# old_kick_line.net
KiCad netlist of a schematic drawn in EAGLE
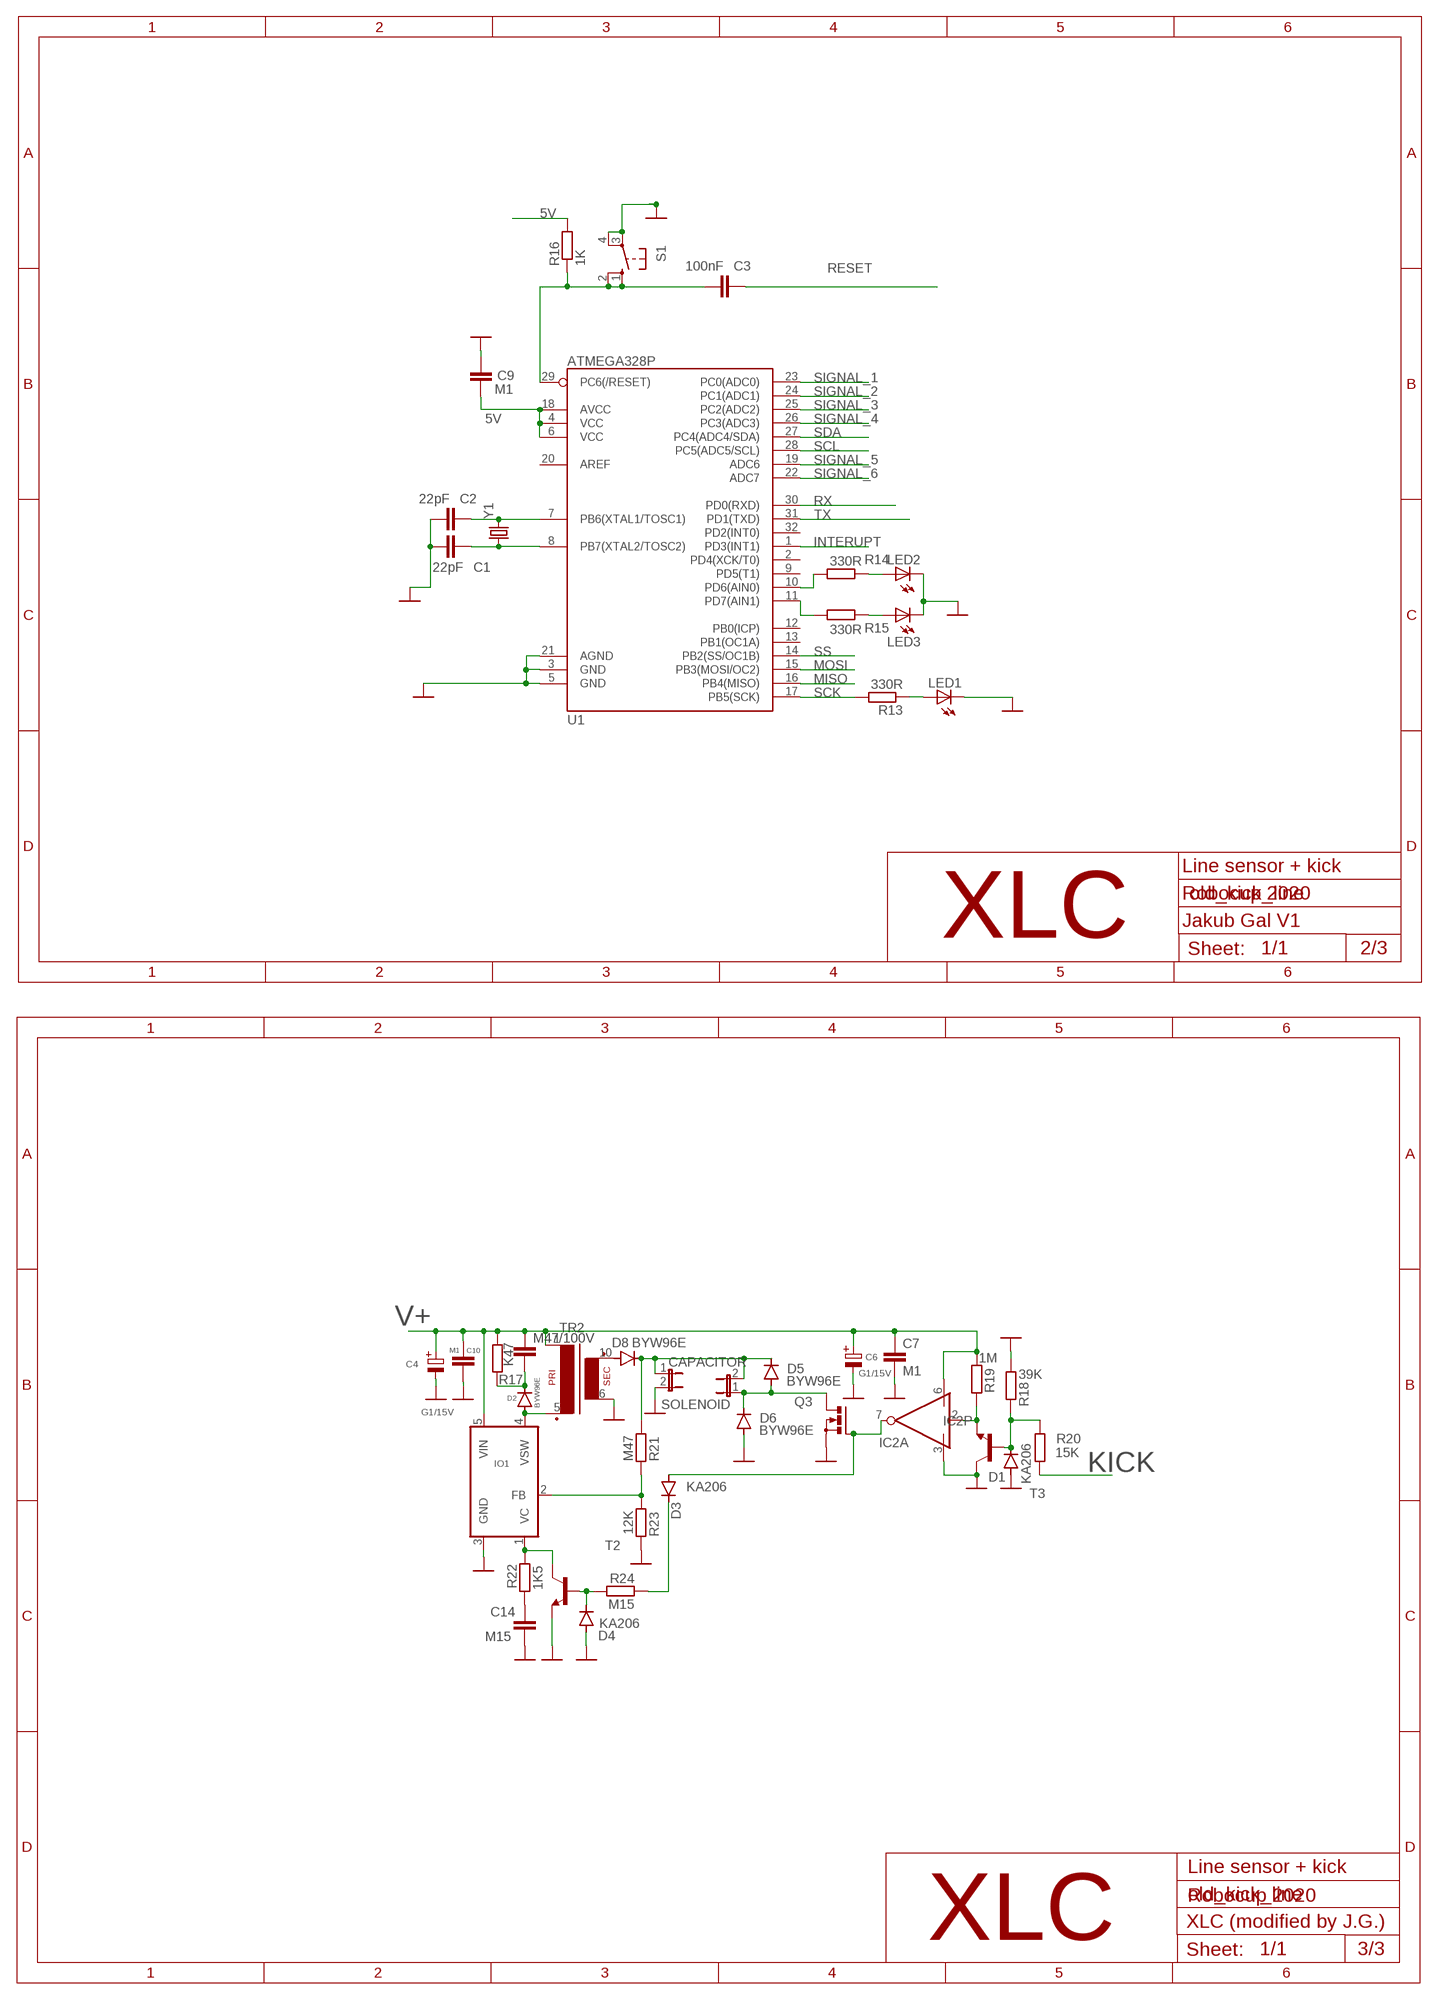
[diagram p0: schematic, sheet 1, part 1 of 2]
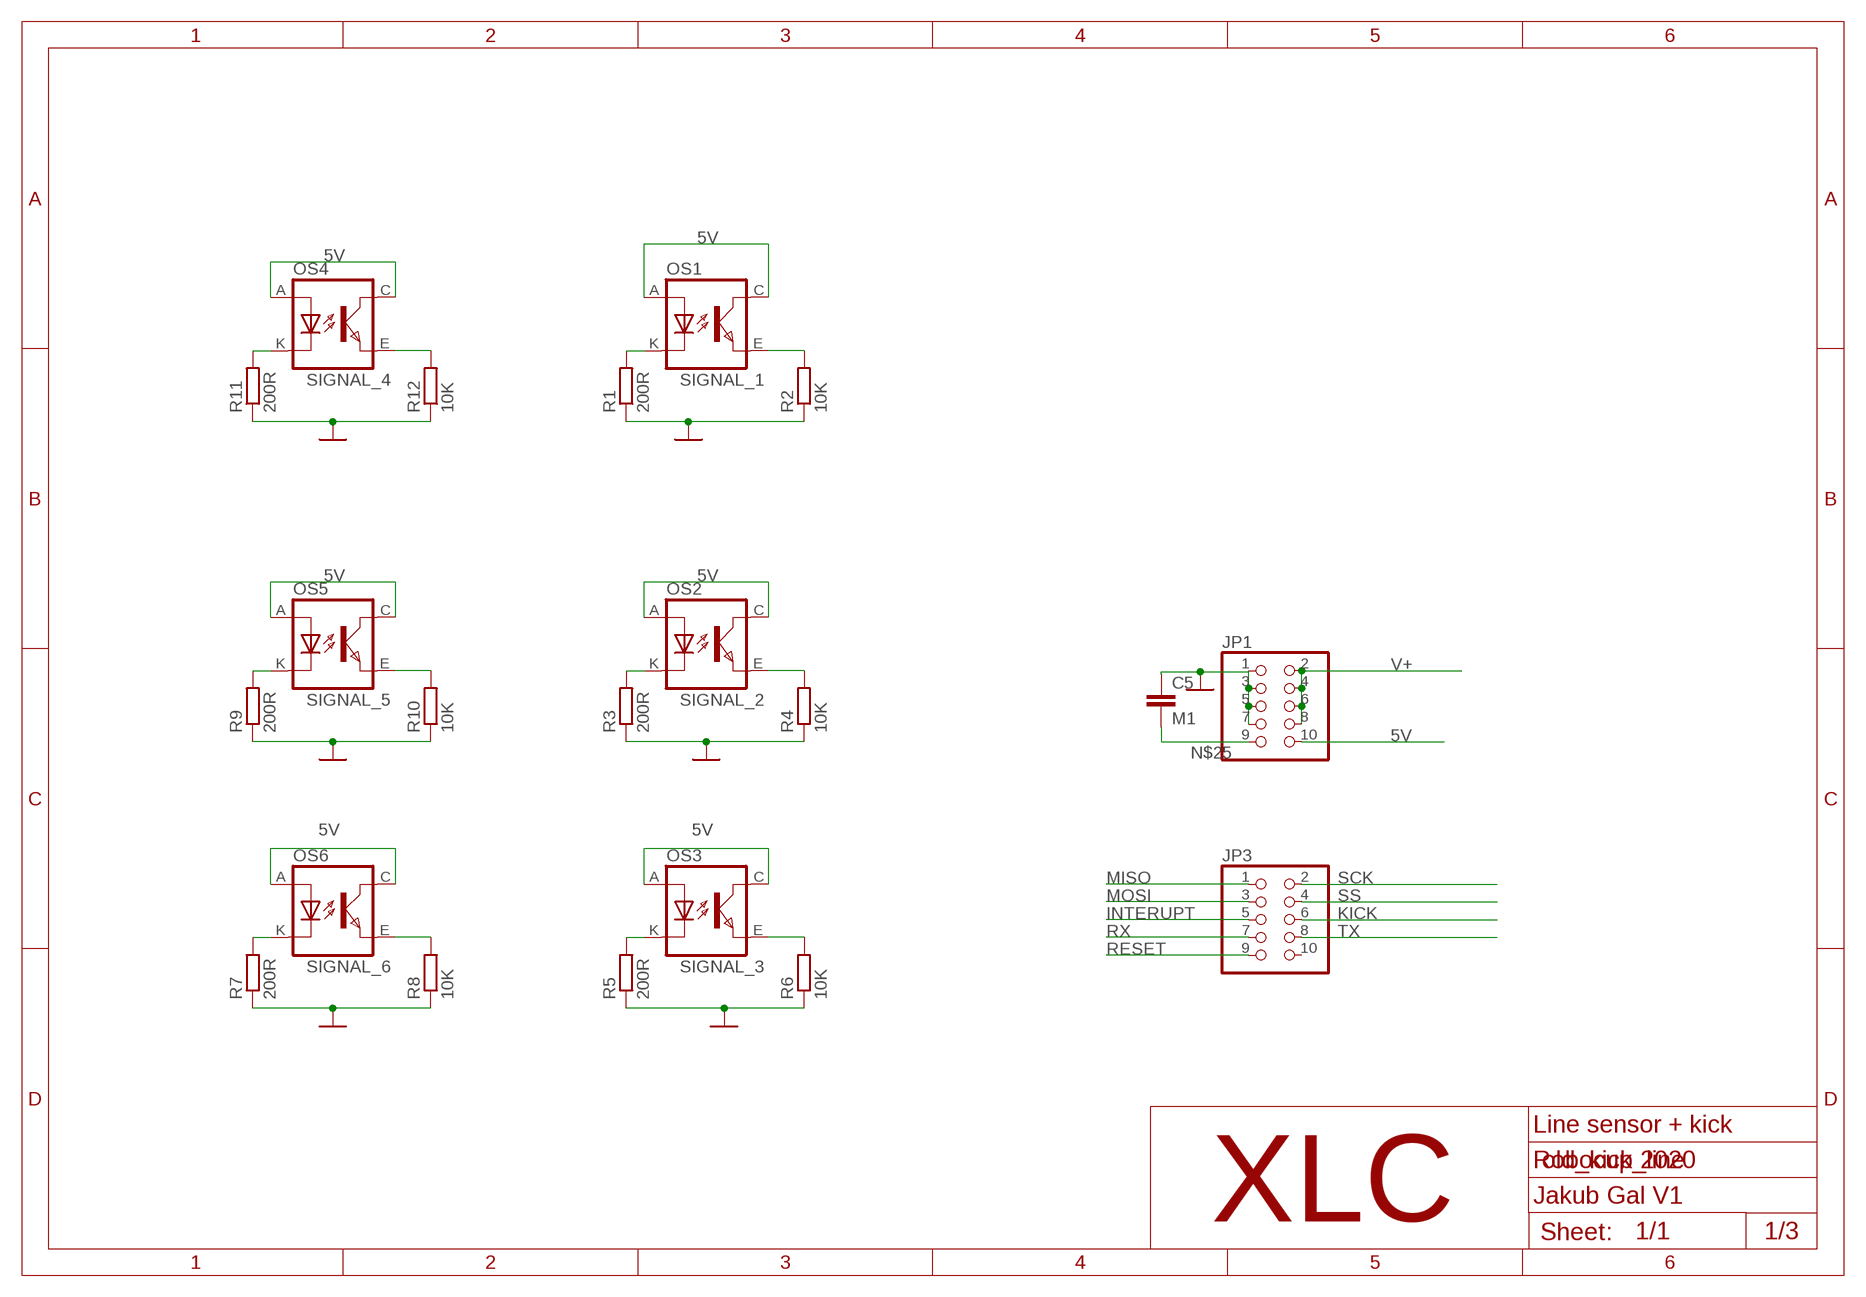
[diagram p1: schematic, sheet 1, part 2 of 2]

(export (version "E")
  (design (tool "Eeschema 10.0.6"))
  (components
    (comp (ref "C1")
      (value "22pF")
      (footprint "eagle-import:C0603")
      (libsource (lib "eagle-import") (part "rcl@1_C-EUC0603"))
    )
    (comp (ref "C2")
      (value "22pF")
      (footprint "eagle-import:C0603")
      (libsource (lib "eagle-import") (part "rcl@1_C-EUC0603"))
    )
    (comp (ref "C3")
      (value "100nF")
      (footprint "eagle-import:C0603")
      (libsource (lib "eagle-import") (part "rcl@1_C-EUC0603"))
    )
    (comp (ref "C4")
      (value "G1/15V")
      (footprint "eagle-import:E-2,5_7-RAD")
      (libsource (lib "eagle-import") (part "KOND-ELEKT-2,5/7"))
    )
    (comp (ref "C5")
      (value "M1")
      (footprint "eagle-import:C0603")
      (libsource (lib "eagle-import") (part "C-EUC0603"))
    )
    (comp (ref "C6")
      (value "G1/15V")
      (footprint "eagle-import:E-2,5_7-RAD")
      (libsource (lib "eagle-import") (part "KOND-ELEKT-2,5/7"))
    )
    (comp (ref "C7")
      (value "M1")
      (footprint "eagle-import:C0805K")
      (libsource (lib "eagle-import") (part "resistor_C-EUC0805K"))
    )
    (comp (ref "C9")
      (value "M1")
      (footprint "eagle-import:C0603")
      (libsource (lib "eagle-import") (part "rcl@1_C-EUC0603"))
    )
    (comp (ref "C10")
      (value "M1")
      (footprint "eagle-import:C0805K")
      (libsource (lib "eagle-import") (part "resistor_C-EUC0805K"))
    )
    (comp (ref "C14")
      (value "M15")
      (footprint "eagle-import:C0805K")
      (libsource (lib "eagle-import") (part "resistor_C-EUC0805K"))
    )
    (comp (ref "CAPACITOR")
      (value "JP1E")
      (footprint "eagle-import:JP1")
      (libsource (lib "eagle-import") (part "JP1E"))
    )
    (comp (ref "D1")
      (value "KA206")
      (footprint "eagle-import:D-7.5")
      (libsource (lib "eagle-import") (part "DIODE-D-7.5"))
    )
    (comp (ref "D2")
      (value "BYW96E")
      (footprint "eagle-import:SOD64-10")
      (libsource (lib "eagle-import") (part "BYW96"))
    )
    (comp (ref "D3")
      (value "KA206")
      (footprint "eagle-import:D-7.5")
      (libsource (lib "eagle-import") (part "DIODE-D-7.5"))
    )
    (comp (ref "D4")
      (value "KA206")
      (footprint "eagle-import:D-7.5")
      (libsource (lib "eagle-import") (part "DIODE-D-7.5"))
    )
    (comp (ref "D5")
      (value "BYW96E")
      (footprint "eagle-import:SOD64-10")
      (libsource (lib "eagle-import") (part "BYW96"))
    )
    (comp (ref "D6")
      (value "BYW96E")
      (footprint "eagle-import:SOD64-10")
      (libsource (lib "eagle-import") (part "BYW96"))
    )
    (comp (ref "D8")
      (value "BYW96E")
      (footprint "eagle-import:SOD64-10")
      (libsource (lib "eagle-import") (part "BYW96"))
    )
    (comp (ref "IC2")
      (value "MIC4423BM")
      (footprint "eagle-import:SO08")
      (libsource (lib "eagle-import") (part "MIC4423BM"))
    )
    (comp (ref "IO1")
      (value "LT1071V")
      (footprint "eagle-import:TO220-5P")
      (libsource (lib "eagle-import") (part "LT1071V"))
    )
    (comp (ref "JP1")
      (value "PINHD-2X5IDC")
      (footprint "eagle-import:2X05_IDC")
      (libsource (lib "eagle-import") (part "PINHD-2X5IDC"))
    )
    (comp (ref "JP3")
      (value "PINHD-2X5IDC")
      (footprint "eagle-import:2X05_IDC")
      (libsource (lib "eagle-import") (part "PINHD-2X5IDC"))
    )
    (comp (ref "LED1")
      (value "LEDCHIPLED_0603")
      (footprint "eagle-import:CHIPLED_0603")
      (libsource (lib "eagle-import") (part "LEDCHIPLED_0603"))
    )
    (comp (ref "LED2")
      (value "LEDCHIPLED_0603")
      (footprint "eagle-import:CHIPLED_0603")
      (libsource (lib "eagle-import") (part "LEDCHIPLED_0603"))
    )
    (comp (ref "LED3")
      (value "LEDCHIPLED_0603")
      (footprint "eagle-import:CHIPLED_0603")
      (libsource (lib "eagle-import") (part "LEDCHIPLED_0603"))
    )
    (comp (ref "M47/100V")
      (value "C-EUC0805K")
      (footprint "eagle-import:C0805K")
      (libsource (lib "eagle-import") (part "resistor_C-EUC0805K"))
    )
    (comp (ref "OS1")
      (value "TCRT5000")
      (footprint "eagle-import:TCRT5000")
      (libsource (lib "eagle-import") (part "TCRT5000"))
    )
    (comp (ref "OS2")
      (value "TCRT5000")
      (footprint "eagle-import:TCRT5000")
      (libsource (lib "eagle-import") (part "TCRT5000"))
    )
    (comp (ref "OS3")
      (value "TCRT5000")
      (footprint "eagle-import:TCRT5000")
      (libsource (lib "eagle-import") (part "TCRT5000"))
    )
    (comp (ref "OS4")
      (value "TCRT5000")
      (footprint "eagle-import:TCRT5000")
      (fields (field (name "SPICEPREFIX") "O"))
      (libsource (lib "eagle-import") (part "TCRT5000"))
    )
    (comp (ref "OS5")
      (value "TCRT5000")
      (footprint "eagle-import:TCRT5000")
      (libsource (lib "eagle-import") (part "TCRT5000"))
    )
    (comp (ref "OS6")
      (value "TCRT5000")
      (footprint "eagle-import:TCRT5000")
      (fields (field (name "SPICEPREFIX") "O"))
      (libsource (lib "eagle-import") (part "TCRT5000"))
    )
    (comp (ref "Q3")
      (value "PMOSFET_NTO220BV")
      (footprint "eagle-import:TO220BV")
      (libsource (lib "eagle-import") (part "PMOSFET_NTO220BV"))
    )
    (comp (ref "R1")
      (value "200R")
      (footprint "eagle-import:R0603")
      (libsource (lib "eagle-import") (part "R-EU_R0603"))
    )
    (comp (ref "R2")
      (value "10K")
      (footprint "eagle-import:R0603")
      (libsource (lib "eagle-import") (part "R-EU_R0603"))
    )
    (comp (ref "R3")
      (value "200R")
      (footprint "eagle-import:R0603")
      (libsource (lib "eagle-import") (part "R-EU_R0603"))
    )
    (comp (ref "R4")
      (value "10K")
      (footprint "eagle-import:R0603")
      (libsource (lib "eagle-import") (part "R-EU_R0603"))
    )
    (comp (ref "R5")
      (value "200R")
      (footprint "eagle-import:R0603")
      (libsource (lib "eagle-import") (part "R-EU_R0603"))
    )
    (comp (ref "R6")
      (value "10K")
      (footprint "eagle-import:R0603")
      (libsource (lib "eagle-import") (part "R-EU_R0603"))
    )
    (comp (ref "R7")
      (value "200R")
      (footprint "eagle-import:R0603")
      (libsource (lib "eagle-import") (part "R-EU_R0603"))
    )
    (comp (ref "R8")
      (value "10K")
      (footprint "eagle-import:R0603")
      (libsource (lib "eagle-import") (part "R-EU_R0603"))
    )
    (comp (ref "R9")
      (value "200R")
      (footprint "eagle-import:R0603")
      (libsource (lib "eagle-import") (part "R-EU_R0603"))
    )
    (comp (ref "R10")
      (value "10K")
      (footprint "eagle-import:R0603")
      (libsource (lib "eagle-import") (part "R-EU_R0603"))
    )
    (comp (ref "R11")
      (value "200R")
      (footprint "eagle-import:R0603")
      (libsource (lib "eagle-import") (part "R-EU_R0603"))
    )
    (comp (ref "R12")
      (value "10K")
      (footprint "eagle-import:R0603")
      (libsource (lib "eagle-import") (part "R-EU_R0603"))
    )
    (comp (ref "R13")
      (value "330R")
      (footprint "eagle-import:R0603")
      (libsource (lib "eagle-import") (part "R-EU_R0603"))
    )
    (comp (ref "R14")
      (value "330R")
      (footprint "eagle-import:R0603")
      (libsource (lib "eagle-import") (part "R-EU_R0603"))
    )
    (comp (ref "R15")
      (value "330R")
      (footprint "eagle-import:R0603")
      (libsource (lib "eagle-import") (part "R-EU_R0603"))
    )
    (comp (ref "R16")
      (value "1K")
      (footprint "eagle-import:R0603")
      (libsource (lib "eagle-import") (part "R-EU_R0603"))
    )
    (comp (ref "R17")
      (value "K47")
      (footprint "eagle-import:R0603")
      (libsource (lib "eagle-import") (part "resistor_R-EU_R0603"))
    )
    (comp (ref "R18")
      (value "39K")
      (footprint "eagle-import:R0603")
      (libsource (lib "eagle-import") (part "resistor_R-EU_R0603"))
    )
    (comp (ref "R19")
      (value "1M")
      (footprint "eagle-import:R0603")
      (libsource (lib "eagle-import") (part "resistor_R-EU_R0603"))
    )
    (comp (ref "R20")
      (value "15K")
      (footprint "eagle-import:R0603")
      (libsource (lib "eagle-import") (part "resistor_R-EU_R0603"))
    )
    (comp (ref "R21")
      (value "M47")
      (footprint "eagle-import:R0603")
      (libsource (lib "eagle-import") (part "resistor_R-EU_R0603"))
    )
    (comp (ref "R22")
      (value "1K5")
      (footprint "eagle-import:R0603")
      (libsource (lib "eagle-import") (part "resistor_R-EU_R0603"))
    )
    (comp (ref "R23")
      (value "12K")
      (footprint "eagle-import:R0603")
      (libsource (lib "eagle-import") (part "resistor_R-EU_R0603"))
    )
    (comp (ref "R24")
      (value "M15")
      (footprint "eagle-import:R0603")
      (libsource (lib "eagle-import") (part "resistor_R-EU_R0603"))
    )
    (comp (ref "S1")
      (value "10-XX")
      (footprint "eagle-import:B3F-10XX")
      (fields (field (name "MPN") "B3F-1000"))
      (libsource (lib "eagle-import") (part "10-XX"))
    )
    (comp (ref "SOLENOID")
      (value "JP1E")
      (footprint "eagle-import:JP1")
      (libsource (lib "eagle-import") (part "JP1E"))
    )
    (comp (ref "T2")
      (value "-NPN-SC59-BEC")
      (footprint "eagle-import:SC59-BEC")
      (libsource (lib "eagle-import") (part "-NPN-SC59-BEC"))
    )
    (comp (ref "T3")
      (value "-NPN-SC59-BEC")
      (footprint "eagle-import:SC59-BEC")
      (libsource (lib "eagle-import") (part "-NPN-SC59-BEC"))
    )
    (comp (ref "TR2")
      (value "TRAFO-E10-R\"\"")
      (footprint "eagle-import:TRAFO-EE17X20")
      (libsource (lib "eagle-import") (part "TRAFO-E10-R{dblquote}{dblquote}"))
    )
    (comp (ref "U1")
      (value "ATMEGA328P")
      (footprint "eagle-import:TQFP32-08")
      (libsource (lib "eagle-import") (part "ATMEGA328_SMT"))
    )
    (comp (ref "Y1")
      (value "CRYSTALHC49US")
      (footprint "eagle-import:HC49US")
      (libsource (lib "eagle-import") (part "CRYSTALHC49US"))
    )
  )
  (nets
    (net (code "1") (name "/5V") (class "Default")
      (node (ref "C9") (pin "1") (pinfunction "1_1") (pintype "passive"))
      (node (ref "JP1") (pin "10") (pinfunction "10_10") (pintype "passive"))
      (node (ref "OS1") (pin "A") (pinfunction "ANODE_A") (pintype "passive"))
      (node (ref "OS1") (pin "C") (pinfunction "COLLECTOR_C") (pintype "passive"))
      (node (ref "OS2") (pin "A") (pinfunction "ANODE_A") (pintype "passive"))
      (node (ref "OS2") (pin "C") (pinfunction "COLLECTOR_C") (pintype "passive"))
      (node (ref "OS3") (pin "A") (pinfunction "ANODE_A") (pintype "passive"))
      (node (ref "OS3") (pin "C") (pinfunction "COLLECTOR_C") (pintype "passive"))
      (node (ref "OS4") (pin "A") (pinfunction "ANODE_A") (pintype "passive"))
      (node (ref "OS4") (pin "C") (pinfunction "COLLECTOR_C") (pintype "passive"))
      (node (ref "OS5") (pin "A") (pinfunction "ANODE_A") (pintype "passive"))
      (node (ref "OS5") (pin "C") (pinfunction "COLLECTOR_C") (pintype "passive"))
      (node (ref "OS6") (pin "A") (pinfunction "ANODE_A") (pintype "passive"))
      (node (ref "OS6") (pin "C") (pinfunction "COLLECTOR_C") (pintype "passive"))
      (node (ref "R16") (pin "2") (pinfunction "2_2") (pintype "passive"))
      (node (ref "U1") (pin "18") (pinfunction "AVCC_18") (pintype "bidirectional"))
      (node (ref "U1") (pin "4") (pinfunction "VCC_4") (pintype "bidirectional"))
      (node (ref "U1") (pin "6") (pinfunction "VCC_6") (pintype "bidirectional"))
    )
    (net (code "2") (name "/INTERUPT") (class "Default")
      (node (ref "JP3") (pin "5") (pinfunction "5_5") (pintype "passive"))
      (node (ref "U1") (pin "1") (pinfunction "PD3(INT1)_1") (pintype "bidirectional"))
    )
    (net (code "3") (name "/KICK") (class "Default")
      (node (ref "JP3") (pin "6") (pinfunction "6_6") (pintype "passive"))
      (node (ref "R20") (pin "1") (pinfunction "1_1") (pintype "passive"))
    )
    (net (code "4") (name "/MISO") (class "Default")
      (node (ref "JP3") (pin "1") (pinfunction "1_1") (pintype "passive"))
      (node (ref "U1") (pin "16") (pinfunction "PB4(MISO)_16") (pintype "bidirectional"))
    )
    (net (code "5") (name "/MOSI") (class "Default")
      (node (ref "JP3") (pin "3") (pinfunction "3_3") (pintype "passive"))
      (node (ref "U1") (pin "15") (pinfunction "PB3(MOSI/OC2)_15") (pintype "bidirectional"))
    )
    (net (code "6") (name "/N$25") (class "Default")
      (node (ref "C5") (pin "2") (pinfunction "2_2") (pintype "passive"))
      (node (ref "JP1") (pin "9") (pinfunction "9_9") (pintype "passive"))
    )
    (net (code "7") (name "/RESET") (class "Default")
      (node (ref "C3") (pin "2") (pinfunction "2_2") (pintype "passive"))
      (node (ref "JP3") (pin "9") (pinfunction "9_9") (pintype "passive"))
    )
    (net (code "8") (name "/RX") (class "Default")
      (node (ref "JP3") (pin "7") (pinfunction "7_7") (pintype "passive"))
      (node (ref "U1") (pin "30") (pinfunction "PD0(RXD)_30") (pintype "bidirectional"))
    )
    (net (code "9") (name "/SCK") (class "Default")
      (node (ref "JP3") (pin "2") (pinfunction "2_2") (pintype "passive"))
      (node (ref "R13") (pin "2") (pinfunction "2_2") (pintype "passive"))
      (node (ref "U1") (pin "17") (pinfunction "PB5(SCK)_17") (pintype "bidirectional"))
    )
    (net (code "10") (name "/SCL") (class "Default")
      (node (ref "U1") (pin "28") (pinfunction "PC5(ADC5/SCL)_28") (pintype "bidirectional"))
    )
    (net (code "11") (name "/SDA") (class "Default")
      (node (ref "U1") (pin "27") (pinfunction "PC4(ADC4/SDA)_27") (pintype "bidirectional"))
    )
    (net (code "12") (name "/SIGNAL_1") (class "Default")
      (node (ref "OS1") (pin "E") (pinfunction "EMITTER_E") (pintype "passive"))
      (node (ref "R2") (pin "2") (pinfunction "2_2") (pintype "passive"))
      (node (ref "U1") (pin "23") (pinfunction "PC0(ADC0)_23") (pintype "bidirectional"))
    )
    (net (code "13") (name "/SIGNAL_2") (class "Default")
      (node (ref "OS2") (pin "E") (pinfunction "EMITTER_E") (pintype "passive"))
      (node (ref "R4") (pin "2") (pinfunction "2_2") (pintype "passive"))
      (node (ref "U1") (pin "24") (pinfunction "PC1(ADC1)_24") (pintype "bidirectional"))
    )
    (net (code "14") (name "/SIGNAL_3") (class "Default")
      (node (ref "OS3") (pin "E") (pinfunction "EMITTER_E") (pintype "passive"))
      (node (ref "R6") (pin "2") (pinfunction "2_2") (pintype "passive"))
      (node (ref "U1") (pin "25") (pinfunction "PC2(ADC2)_25") (pintype "bidirectional"))
    )
    (net (code "15") (name "/SIGNAL_4") (class "Default")
      (node (ref "OS4") (pin "E") (pinfunction "EMITTER_E") (pintype "passive"))
      (node (ref "R12") (pin "2") (pinfunction "2_2") (pintype "passive"))
      (node (ref "U1") (pin "26") (pinfunction "PC3(ADC3)_26") (pintype "bidirectional"))
    )
    (net (code "16") (name "/SIGNAL_5") (class "Default")
      (node (ref "OS5") (pin "E") (pinfunction "EMITTER_E") (pintype "passive"))
      (node (ref "R10") (pin "2") (pinfunction "2_2") (pintype "passive"))
      (node (ref "U1") (pin "19") (pinfunction "ADC6_19") (pintype "bidirectional"))
    )
    (net (code "17") (name "/SIGNAL_6") (class "Default")
      (node (ref "OS6") (pin "E") (pinfunction "EMITTER_E") (pintype "passive"))
      (node (ref "R8") (pin "2") (pinfunction "2_2") (pintype "passive"))
      (node (ref "U1") (pin "22") (pinfunction "ADC7_22") (pintype "bidirectional"))
    )
    (net (code "18") (name "/SS") (class "Default")
      (node (ref "JP3") (pin "4") (pinfunction "4_4") (pintype "passive"))
      (node (ref "U1") (pin "14") (pinfunction "PB2(SS/OC1B)_14") (pintype "bidirectional"))
    )
    (net (code "19") (name "/TX") (class "Default")
      (node (ref "JP3") (pin "8") (pinfunction "8_8") (pintype "passive"))
      (node (ref "U1") (pin "31") (pinfunction "PD1(TXD)_31") (pintype "bidirectional"))
    )
    (net (code "20") (name "/V+") (class "Default")
      (node (ref "C10") (pin "1") (pinfunction "1_1") (pintype "passive"))
      (node (ref "C4") (pin "+") (pinfunction "+_+") (pintype "passive"))
      (node (ref "C6") (pin "+") (pinfunction "+_+") (pintype "passive"))
      (node (ref "C7") (pin "1") (pinfunction "1_1") (pintype "passive"))
      (node (ref "IC2") (pin "6") (pinfunction "V+_6") (pintype "power_in"))
      (node (ref "IO1") (pin "5") (pinfunction "VIN_5") (pintype "power_in"))
      (node (ref "JP1") (pin "2") (pinfunction "2_2") (pintype "passive"))
      (node (ref "JP1") (pin "4") (pinfunction "4_4") (pintype "passive"))
      (node (ref "JP1") (pin "6") (pinfunction "6_6") (pintype "passive"))
      (node (ref "JP1") (pin "8") (pinfunction "8_8") (pintype "passive"))
      (node (ref "M47/100V") (pin "1") (pinfunction "1_1") (pintype "passive"))
      (node (ref "R17") (pin "1") (pinfunction "1_1") (pintype "passive"))
      (node (ref "R19") (pin "2") (pinfunction "2_2") (pintype "passive"))
      (node (ref "TR2") (pin "1") (pinfunction "1_1") (pintype "passive"))
    )
    (net (code "21") (name "GND") (class "Default")
      (node (ref "C1") (pin "1") (pinfunction "1_1") (pintype "passive"))
      (node (ref "C10") (pin "2") (pinfunction "2_2") (pintype "passive"))
      (node (ref "C14") (pin "2") (pinfunction "2_2") (pintype "passive"))
      (node (ref "C2") (pin "1") (pinfunction "1_1") (pintype "passive"))
      (node (ref "C4") (pin "-") (pinfunction "-_-") (pintype "passive"))
      (node (ref "C5") (pin "1") (pinfunction "1_1") (pintype "passive"))
      (node (ref "C6") (pin "-") (pinfunction "-_-") (pintype "passive"))
      (node (ref "C7") (pin "2") (pinfunction "2_2") (pintype "passive"))
      (node (ref "C9") (pin "2") (pinfunction "2_2") (pintype "passive"))
      (node (ref "CAPACITOR") (pin "2") (pinfunction "2_2") (pintype "passive"))
      (node (ref "D1") (pin "A") (pinfunction "A_A") (pintype "passive"))
      (node (ref "D4") (pin "A") (pinfunction "A_A") (pintype "passive"))
      (node (ref "D6") (pin "A") (pinfunction "A_A") (pintype "passive"))
      (node (ref "IC2") (pin "3") (pinfunction "GND_3") (pintype "power_in"))
      (node (ref "IO1") (pin "3") (pinfunction "GND_3") (pintype "power_in"))
      (node (ref "JP1") (pin "1") (pinfunction "1_1") (pintype "passive"))
      (node (ref "JP1") (pin "3") (pinfunction "3_3") (pintype "passive"))
      (node (ref "JP1") (pin "5") (pinfunction "5_5") (pintype "passive"))
      (node (ref "JP1") (pin "7") (pinfunction "7_7") (pintype "passive"))
      (node (ref "LED1") (pin "C") (pinfunction "C_C") (pintype "passive"))
      (node (ref "LED2") (pin "C") (pinfunction "C_C") (pintype "passive"))
      (node (ref "LED3") (pin "C") (pinfunction "C_C") (pintype "passive"))
      (node (ref "Q3") (pin "S") (pinfunction "S_S") (pintype "passive"))
      (node (ref "R1") (pin "1") (pinfunction "1_1") (pintype "passive"))
      (node (ref "R10") (pin "1") (pinfunction "1_1") (pintype "passive"))
      (node (ref "R11") (pin "1") (pinfunction "1_1") (pintype "passive"))
      (node (ref "R12") (pin "1") (pinfunction "1_1") (pintype "passive"))
      (node (ref "R18") (pin "2") (pinfunction "2_2") (pintype "passive"))
      (node (ref "R2") (pin "1") (pinfunction "1_1") (pintype "passive"))
      (node (ref "R23") (pin "1") (pinfunction "1_1") (pintype "passive"))
      (node (ref "R3") (pin "1") (pinfunction "1_1") (pintype "passive"))
      (node (ref "R4") (pin "1") (pinfunction "1_1") (pintype "passive"))
      (node (ref "R5") (pin "1") (pinfunction "1_1") (pintype "passive"))
      (node (ref "R6") (pin "1") (pinfunction "1_1") (pintype "passive"))
      (node (ref "R7") (pin "1") (pinfunction "1_1") (pintype "passive"))
      (node (ref "R8") (pin "1") (pinfunction "1_1") (pintype "passive"))
      (node (ref "R9") (pin "1") (pinfunction "1_1") (pintype "passive"))
      (node (ref "S1") (pin "3") (pinfunction "P_3") (pintype "passive"))
      (node (ref "S1") (pin "4") (pinfunction "P1_4") (pintype "passive"))
      (node (ref "T2") (pin "E") (pinfunction "E_E") (pintype "passive"))
      (node (ref "T3") (pin "C") (pinfunction "C_C") (pintype "passive"))
      (node (ref "TR2") (pin "6") (pinfunction "3_6") (pintype "passive"))
      (node (ref "U1") (pin "21") (pinfunction "AGND_21") (pintype "bidirectional"))
      (node (ref "U1") (pin "3") (pinfunction "GND_3") (pintype "bidirectional"))
      (node (ref "U1") (pin "5") (pinfunction "GND_5") (pintype "bidirectional"))
    )
    (net (code "22") (name "Net-(C14-Pad1)") (class "Default")
      (node (ref "C14") (pin "1") (pinfunction "1_1") (pintype "passive"))
      (node (ref "R22") (pin "2") (pinfunction "2_2") (pintype "passive"))
    )
    (net (code "23") (name "Net-(CAPACITOR-Pad1)") (class "Default")
      (node (ref "CAPACITOR") (pin "1") (pinfunction "1_1") (pintype "passive"))
      (node (ref "D5") (pin "C") (pinfunction "C_C") (pintype "passive"))
      (node (ref "D8") (pin "C") (pinfunction "C_C") (pintype "passive"))
      (node (ref "R21") (pin "2") (pinfunction "2_2") (pintype "passive"))
      (node (ref "SOLENOID") (pin "2") (pinfunction "2_2") (pintype "passive"))
    )
    (net (code "24") (name "Net-(D1-PadC)") (class "Default")
      (node (ref "D1") (pin "C") (pinfunction "C_C") (pintype "passive"))
      (node (ref "R18") (pin "1") (pinfunction "1_1") (pintype "passive"))
      (node (ref "R20") (pin "2") (pinfunction "2_2") (pintype "passive"))
      (node (ref "T3") (pin "B") (pinfunction "B_B") (pintype "passive"))
    )
    (net (code "25") (name "Net-(D2-PadC)") (class "Default")
      (node (ref "D2") (pin "C") (pinfunction "C_C") (pintype "passive"))
      (node (ref "M47/100V") (pin "2") (pinfunction "2_2") (pintype "passive"))
      (node (ref "R17") (pin "2") (pinfunction "2_2") (pintype "passive"))
    )
    (net (code "26") (name "Net-(D3-PadC)") (class "Default")
      (node (ref "D3") (pin "C") (pinfunction "C_C") (pintype "passive"))
      (node (ref "R24") (pin "1") (pinfunction "1_1") (pintype "passive"))
    )
    (net (code "27") (name "Net-(D4-PadC)") (class "Default")
      (node (ref "D4") (pin "C") (pinfunction "C_C") (pintype "passive"))
      (node (ref "R24") (pin "2") (pinfunction "2_2") (pintype "passive"))
      (node (ref "T2") (pin "B") (pinfunction "B_B") (pintype "passive"))
    )
    (net (code "28") (name "Net-(D5-PadA)") (class "Default")
      (node (ref "D5") (pin "A") (pinfunction "A_A") (pintype "passive"))
      (node (ref "D6") (pin "C") (pinfunction "C_C") (pintype "passive"))
      (node (ref "Q3") (pin "D") (pinfunction "D_D") (pintype "passive"))
      (node (ref "SOLENOID") (pin "1") (pinfunction "1_1") (pintype "passive"))
    )
    (net (code "29") (name "Net-(IC2A-IN)") (class "Default")
      (node (ref "IC2") (pin "2") (pinfunction "IN_2") (pintype "input"))
      (node (ref "R19") (pin "1") (pinfunction "1_1") (pintype "passive"))
      (node (ref "T3") (pin "E") (pinfunction "E_E") (pintype "passive"))
    )
    (net (code "30") (name "Net-(IC2A-OUT)") (class "Default")
      (node (ref "D3") (pin "A") (pinfunction "A_A") (pintype "passive"))
      (node (ref "IC2") (pin "7") (pinfunction "OUT_7") (pintype "output"))
      (node (ref "Q3") (pin "G") (pinfunction "G_G") (pintype "passive"))
    )
    (net (code "31") (name "Net-(IO1-FB)") (class "Default")
      (node (ref "IO1") (pin "2") (pinfunction "FB_2") (pintype "input"))
      (node (ref "R21") (pin "1") (pinfunction "1_1") (pintype "passive"))
      (node (ref "R23") (pin "2") (pinfunction "2_2") (pintype "passive"))
    )
    (net (code "32") (name "Net-(IO1-VC)") (class "Default")
      (node (ref "IO1") (pin "1") (pinfunction "VC_1") (pintype "input"))
      (node (ref "R22") (pin "1") (pinfunction "1_1") (pintype "passive"))
      (node (ref "T2") (pin "C") (pinfunction "C_C") (pintype "passive"))
    )
    (net (code "33") (name "Net-(IO1-VSW)") (class "Default")
      (node (ref "D2") (pin "A") (pinfunction "A_A") (pintype "passive"))
      (node (ref "IO1") (pin "4") (pinfunction "VSW_4") (pintype "output"))
      (node (ref "TR2") (pin "5") (pinfunction "2_5") (pintype "passive"))
    )
    (net (code "34") (name "Net-(LED1-PadA)") (class "Default")
      (node (ref "LED1") (pin "A") (pinfunction "A_A") (pintype "passive"))
      (node (ref "R13") (pin "1") (pinfunction "1_1") (pintype "passive"))
    )
    (net (code "35") (name "Net-(LED2-PadA)") (class "Default")
      (node (ref "LED2") (pin "A") (pinfunction "A_A") (pintype "passive"))
      (node (ref "R14") (pin "1") (pinfunction "1_1") (pintype "passive"))
    )
    (net (code "36") (name "Net-(LED3-PadA)") (class "Default")
      (node (ref "LED3") (pin "A") (pinfunction "A_A") (pintype "passive"))
      (node (ref "R15") (pin "1") (pinfunction "1_1") (pintype "passive"))
    )
    (net (code "37") (name "Net-(OS1-CATHODE)") (class "Default")
      (node (ref "OS1") (pin "K") (pinfunction "CATHODE_K") (pintype "passive"))
      (node (ref "R1") (pin "2") (pinfunction "2_2") (pintype "passive"))
    )
    (net (code "38") (name "Net-(OS2-CATHODE)") (class "Default")
      (node (ref "OS2") (pin "K") (pinfunction "CATHODE_K") (pintype "passive"))
      (node (ref "R3") (pin "2") (pinfunction "2_2") (pintype "passive"))
    )
    (net (code "39") (name "Net-(OS3-CATHODE)") (class "Default")
      (node (ref "OS3") (pin "K") (pinfunction "CATHODE_K") (pintype "passive"))
      (node (ref "R5") (pin "2") (pinfunction "2_2") (pintype "passive"))
    )
    (net (code "40") (name "Net-(OS4-CATHODE)") (class "Default")
      (node (ref "OS4") (pin "K") (pinfunction "CATHODE_K") (pintype "passive"))
      (node (ref "R11") (pin "2") (pinfunction "2_2") (pintype "passive"))
    )
    (net (code "41") (name "Net-(OS5-CATHODE)") (class "Default")
      (node (ref "OS5") (pin "K") (pinfunction "CATHODE_K") (pintype "passive"))
      (node (ref "R9") (pin "2") (pinfunction "2_2") (pintype "passive"))
    )
    (net (code "42") (name "Net-(OS6-CATHODE)") (class "Default")
      (node (ref "OS6") (pin "K") (pinfunction "CATHODE_K") (pintype "passive"))
      (node (ref "R7") (pin "2") (pinfunction "2_2") (pintype "passive"))
    )
    (net (code "43") (name "Net-(S1-S)") (class "Default")
      (node (ref "C3") (pin "1") (pinfunction "1_1") (pintype "passive"))
      (node (ref "R16") (pin "1") (pinfunction "1_1") (pintype "passive"))
      (node (ref "S1") (pin "1") (pinfunction "S_1") (pintype "passive"))
      (node (ref "S1") (pin "2") (pinfunction "S1_2") (pintype "passive"))
      (node (ref "U1") (pin "29") (pinfunction "PC6(/RESET)_29") (pintype "bidirectional"))
    )
    (net (code "44") (name "Net-(TR2-4)") (class "Default")
      (node (ref "D8") (pin "A") (pinfunction "A_A") (pintype "passive"))
      (node (ref "TR2") (pin "10") (pinfunction "4_10") (pintype "passive"))
    )
    (net (code "45") (name "Net-(U1-PB6(XTAL1{slash}TOSC1))") (class "Default")
      (node (ref "C2") (pin "2") (pinfunction "2_2") (pintype "passive"))
      (node (ref "U1") (pin "7") (pinfunction "PB6(XTAL1/TOSC1)_7") (pintype "bidirectional"))
      (node (ref "Y1") (pin "2") (pinfunction "2_2") (pintype "passive"))
    )
    (net (code "46") (name "Net-(U1-PB7(XTAL2{slash}TOSC2))") (class "Default")
      (node (ref "C1") (pin "2") (pinfunction "2_2") (pintype "passive"))
      (node (ref "U1") (pin "8") (pinfunction "PB7(XTAL2/TOSC2)_8") (pintype "bidirectional"))
      (node (ref "Y1") (pin "1") (pinfunction "1_1") (pintype "passive"))
    )
    (net (code "47") (name "Net-(U1-PD6(AIN0))") (class "Default")
      (node (ref "R14") (pin "2") (pinfunction "2_2") (pintype "passive"))
      (node (ref "U1") (pin "10") (pinfunction "PD6(AIN0)_10") (pintype "bidirectional"))
    )
    (net (code "48") (name "Net-(U1-PD7(AIN1))") (class "Default")
      (node (ref "R15") (pin "2") (pinfunction "2_2") (pintype "passive"))
      (node (ref "U1") (pin "11") (pinfunction "PD7(AIN1)_11") (pintype "bidirectional"))
    )
    (net (code "49") (name "unconnected-(JP3-Pad10)") (class "Default")
      (node (ref "JP3") (pin "10") (pinfunction "10_10") (pintype "passive"))
    )
    (net (code "50") (name "unconnected-(U1-AREF-Pad20)") (class "Default")
      (node (ref "U1") (pin "20") (pinfunction "AREF_20") (pintype "bidirectional"))
    )
    (net (code "51") (name "unconnected-(U1-PB0(ICP)-Pad12)") (class "Default")
      (node (ref "U1") (pin "12") (pinfunction "PB0(ICP)_12") (pintype "bidirectional"))
    )
    (net (code "52") (name "unconnected-(U1-PB1(OC1A)-Pad13)") (class "Default")
      (node (ref "U1") (pin "13") (pinfunction "PB1(OC1A)_13") (pintype "bidirectional"))
    )
    (net (code "53") (name "unconnected-(U1-PD2(INT0)-Pad32)") (class "Default")
      (node (ref "U1") (pin "32") (pinfunction "PD2(INT0)_32") (pintype "bidirectional"))
    )
    (net (code "54") (name "unconnected-(U1-PD4(XCK{slash}T0)-Pad2)") (class "Default")
      (node (ref "U1") (pin "2") (pinfunction "PD4(XCK/T0)_2") (pintype "bidirectional"))
    )
    (net (code "55") (name "unconnected-(U1-PD5(T1)-Pad9)") (class "Default")
      (node (ref "U1") (pin "9") (pinfunction "PD5(T1)_9") (pintype "bidirectional"))
    )
  )
)
